# USB.net
KiCad netlist of a schematic drawn in Altium Designer
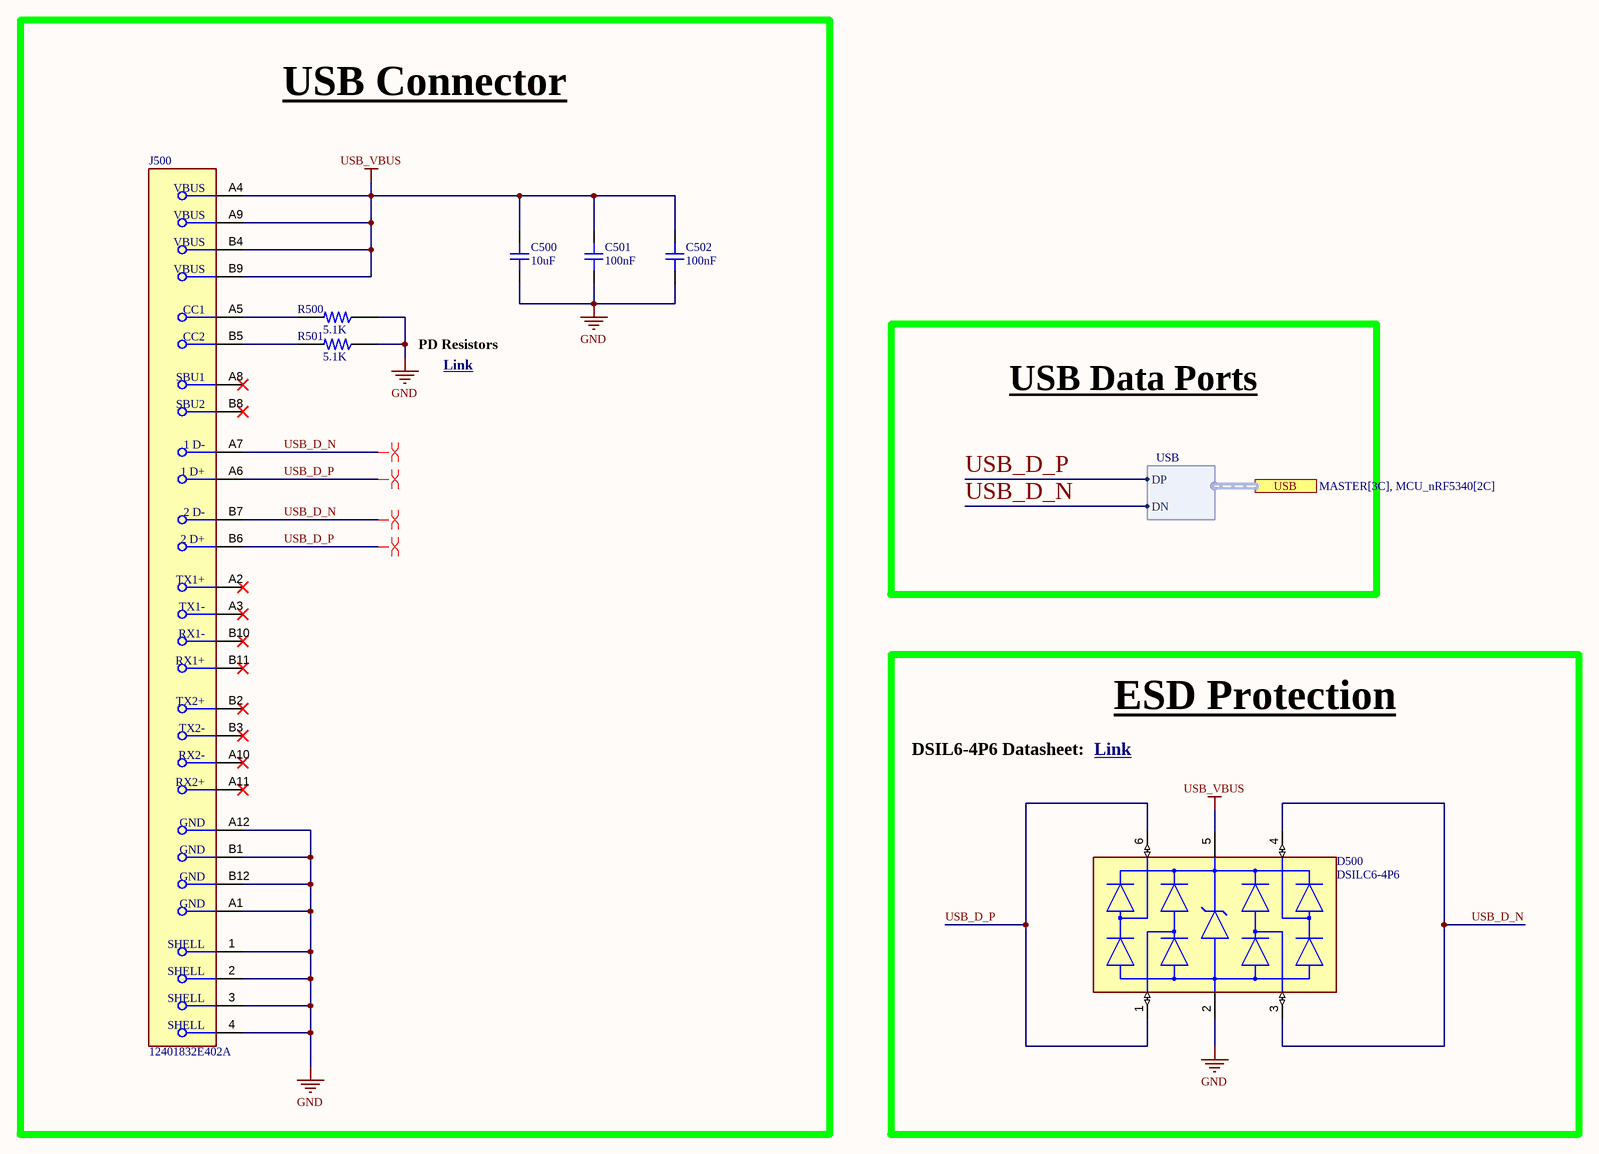
[diagram p0: USB.SchDoc]

(export (version "E")
  (design (tool "Eeschema 10.0.6"))
  (components
    (comp (ref "C500")
      (value "10uF")
      (footprint "CAP_0603")
      (description "Capacitor SMD 0603")
      (libsource (lib "board") (part "CAP_0603"))
    )
    (comp (ref "C501")
      (value "100nF")
      (footprint "CAP_0603")
      (description "Capacitor SMD 0603")
      (libsource (lib "board") (part "CAP_0603"))
    )
    (comp (ref "C502")
      (value "100nF")
      (footprint "CAP_0603")
      (description "Capacitor SMD 0603")
      (libsource (lib "board") (part "CAP_0603"))
    )
    (comp (ref "D500")
      (value "DSILC6-4P6")
      (footprint "FP-SOT-666-MFG")
      (description "TVS DIODE 5V SOT666")
      (fields
        (field (name "OCTOPART") "https://octopart.com/dsilc6-4p6-stmicroelectronics-660265")
        (field (name "MANUFACTURER") "STMicroelectronics")
      )
      (libsource (lib "Altium Content Vault") (part "99bc7c91954861068d5874422266677"))
    )
    (comp (ref "J500")
      (value "12401832E402A")
      (footprint "FP-12401832E402A-MFG")
      (description "CONN RCP USB3.1 TYPEC 24P SMD RA")
      (libsource (lib "Altium Content Vault") (part "50854493bfec571c3c083d899a0df29"))
    )
    (comp (ref "R500")
      (value "5.1K")
      (footprint "RESC1607X60N")
      (description "10 kOhms Â±5% 0.1W, 1/10W Chip Resistor 0603 (1608 Metric) Moisture Resistant Thick Film")
      (fields (field (name "MF") "Yageo") (field (name "MP") "RC0603JR0710KL"))
      (libsource (lib "board") (part "RC0603JR0710KL"))
    )
    (comp (ref "R501")
      (value "5.1K")
      (footprint "RESC1607X60N")
      (description "10 kOhms Â±5% 0.1W, 1/10W Chip Resistor 0603 (1608 Metric) Moisture Resistant Thick Film")
      (fields (field (name "MF") "Yageo") (field (name "MP") "RC0603JR0710KL"))
      (libsource (lib "board") (part "RC0603JR0710KL"))
    )
  )
  (nets
    (net (code "2") (name "/USB_D_N") (class "Default")
      (node (ref "D500") (pin "3") (pinfunction "I/O2_3") (pintype "bidirectional"))
      (node (ref "D500") (pin "4") (pinfunction "I/O3_4") (pintype "bidirectional"))
      (node (ref "J500") (pin "A7") (pinfunction "1_D-_A7") (pintype "passive"))
      (node (ref "J500") (pin "B7") (pinfunction "2_D-_B7") (pintype "passive"))
    )
    (net (code "3") (name "/USB_D_P") (class "Default")
      (node (ref "D500") (pin "1") (pinfunction "I/O1_1") (pintype "bidirectional"))
      (node (ref "D500") (pin "6") (pinfunction "I/O4_6") (pintype "bidirectional"))
      (node (ref "J500") (pin "A6") (pinfunction "1_D+_A6") (pintype "passive"))
      (node (ref "J500") (pin "B6") (pinfunction "2_D+_B6") (pintype "passive"))
    )
    (net (code "5") (name "GND") (class "Default")
      (node (ref "C500") (pin "1") (pinfunction "1_1") (pintype "passive"))
      (node (ref "C501") (pin "1") (pinfunction "1_1") (pintype "passive"))
      (node (ref "C502") (pin "1") (pinfunction "1_1") (pintype "passive"))
      (node (ref "D500") (pin "2") (pinfunction "GND_2") (pintype "power_in"))
      (node (ref "J500") (pin "1") (pinfunction "SHELL_1") (pintype "power_in"))
      (node (ref "J500") (pin "2") (pinfunction "SHELL_2") (pintype "passive"))
      (node (ref "J500") (pin "3") (pinfunction "SHELL_3") (pintype "passive"))
      (node (ref "J500") (pin "4") (pinfunction "SHELL_4") (pintype "power_in"))
      (node (ref "J500") (pin "A1") (pinfunction "GND_A1") (pintype "passive"))
      (node (ref "J500") (pin "A12") (pinfunction "GND_A12") (pintype "power_in"))
      (node (ref "J500") (pin "B1") (pinfunction "GND_B1") (pintype "passive"))
      (node (ref "J500") (pin "B12") (pinfunction "GND_B12") (pintype "power_in"))
      (node (ref "R500") (pin "1") (pinfunction "1_1") (pintype "passive"))
      (node (ref "R501") (pin "1") (pinfunction "1_1") (pintype "passive"))
    )
    (net (code "6") (name "Net-(J500-CC1)") (class "Default")
      (node (ref "J500") (pin "A5") (pinfunction "CC1_A5") (pintype "power_in"))
      (node (ref "R500") (pin "2") (pinfunction "2_2") (pintype "passive"))
    )
    (net (code "7") (name "Net-(J500-CC2)") (class "Default")
      (node (ref "J500") (pin "B5") (pinfunction "CC2_B5") (pintype "power_in"))
      (node (ref "R501") (pin "2") (pinfunction "2_2") (pintype "passive"))
    )
    (net (code "8") (name "USB_VBUS") (class "Default")
      (node (ref "C500") (pin "2") (pinfunction "2_2") (pintype "passive"))
      (node (ref "C501") (pin "2") (pinfunction "2_2") (pintype "passive"))
      (node (ref "C502") (pin "2") (pinfunction "2_2") (pintype "passive"))
      (node (ref "D500") (pin "5") (pinfunction "VCC_5") (pintype "power_in"))
      (node (ref "J500") (pin "A4") (pinfunction "VBUS_A4") (pintype "passive"))
      (node (ref "J500") (pin "A9") (pinfunction "VBUS_A9") (pintype "power_in"))
      (node (ref "J500") (pin "B4") (pinfunction "VBUS_B4") (pintype "passive"))
      (node (ref "J500") (pin "B9") (pinfunction "VBUS_B9") (pintype "power_in"))
    )
    (net (code "9") (name "unconnected-(J500-RX1+-PadB11)") (class "Default")
      (node (ref "J500") (pin "B11") (pinfunction "RX1+_B11") (pintype "power_in+no_connect"))
    )
    (net (code "10") (name "unconnected-(J500-RX1--PadB10)") (class "Default")
      (node (ref "J500") (pin "B10") (pinfunction "RX1-_B10") (pintype "power_in+no_connect"))
    )
    (net (code "11") (name "unconnected-(J500-RX2+-PadA11)") (class "Default")
      (node (ref "J500") (pin "A11") (pinfunction "RX2+_A11") (pintype "passive+no_connect"))
    )
    (net (code "12") (name "unconnected-(J500-RX2--PadA10)") (class "Default")
      (node (ref "J500") (pin "A10") (pinfunction "RX2-_A10") (pintype "passive+no_connect"))
    )
    (net (code "13") (name "unconnected-(J500-SBU1-PadA8)") (class "Default")
      (node (ref "J500") (pin "A8") (pinfunction "SBU1_A8") (pintype "power_in+no_connect"))
    )
    (net (code "14") (name "unconnected-(J500-SBU2-PadB8)") (class "Default")
      (node (ref "J500") (pin "B8") (pinfunction "SBU2_B8") (pintype "power_in+no_connect"))
    )
    (net (code "15") (name "unconnected-(J500-TX1+-PadA2)") (class "Default")
      (node (ref "J500") (pin "A2") (pinfunction "TX1+_A2") (pintype "passive+no_connect"))
    )
    (net (code "16") (name "unconnected-(J500-TX1--PadA3)") (class "Default")
      (node (ref "J500") (pin "A3") (pinfunction "TX1-_A3") (pintype "passive+no_connect"))
    )
    (net (code "17") (name "unconnected-(J500-TX2+-PadB2)") (class "Default")
      (node (ref "J500") (pin "B2") (pinfunction "TX2+_B2") (pintype "passive+no_connect"))
    )
    (net (code "18") (name "unconnected-(J500-TX2--PadB3)") (class "Default")
      (node (ref "J500") (pin "B3") (pinfunction "TX2-_B3") (pintype "passive+no_connect"))
    )
  )
)
